# teensy3_5dds.net
KiCad netlist of a schematic drawn in EAGLE
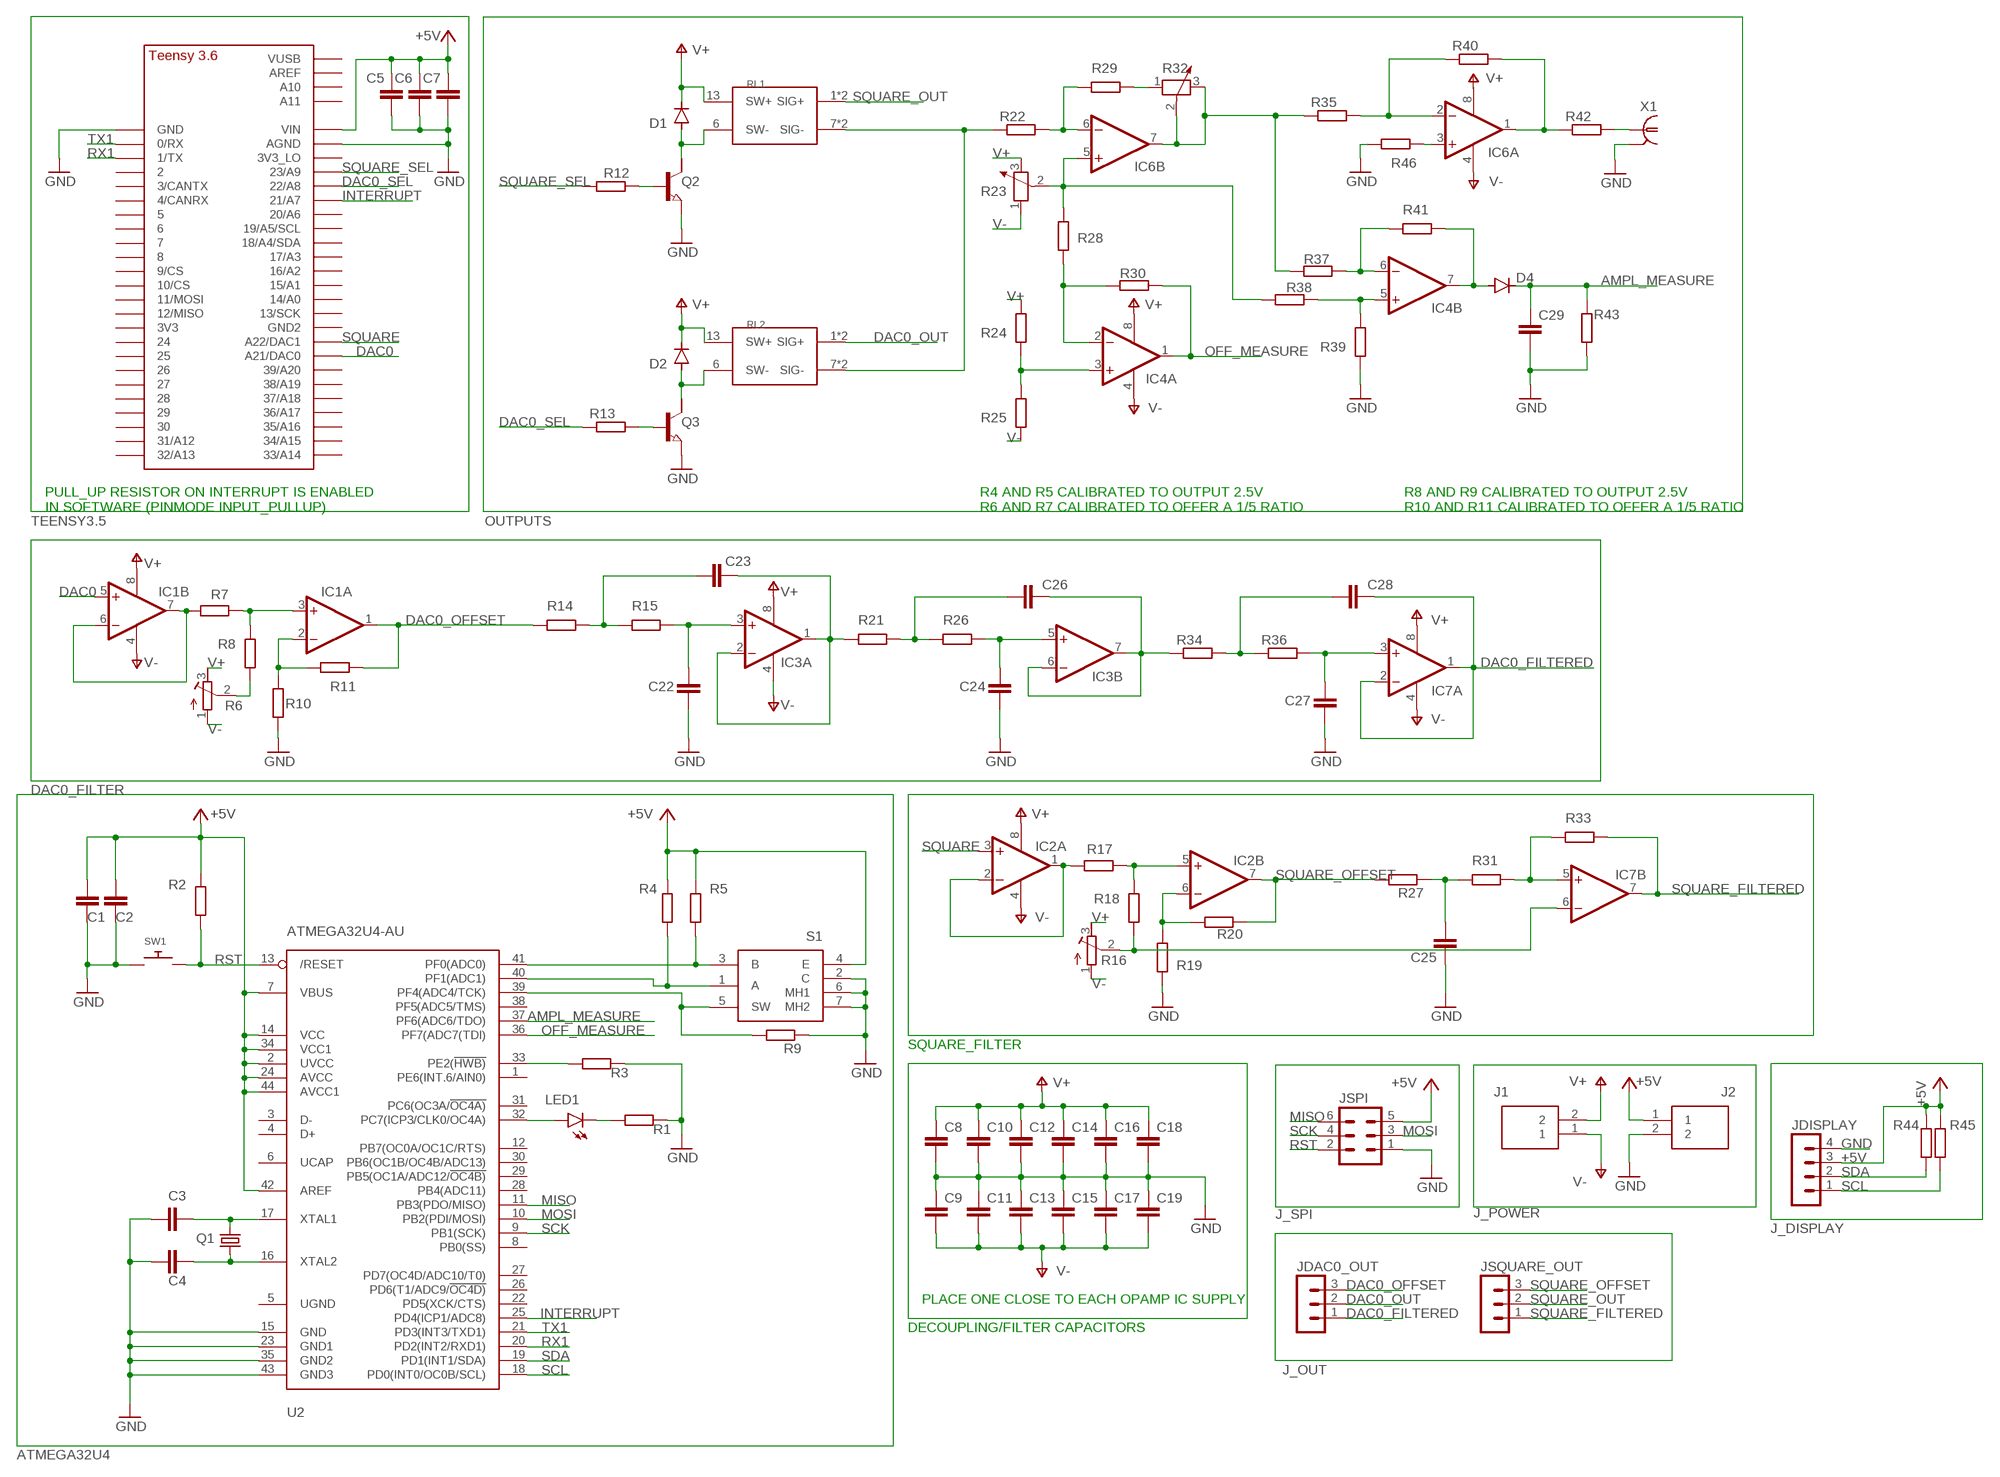
[diagram p0: schematic, sheet 1]

(export (version "E")
  (design (tool "Eeschema 10.0.6"))
  (components
    (comp (ref "C1")
      (value "100u")
      (footprint "eagle-import:C1206")
      (libsource (lib "eagle-import") (part "C-EUC1206"))
    )
    (comp (ref "C2")
      (value "100n")
      (footprint "eagle-import:C0805")
      (libsource (lib "eagle-import") (part "C-EUC0805"))
    )
    (comp (ref "C3")
      (value "22p")
      (footprint "eagle-import:C0805")
      (libsource (lib "eagle-import") (part "C-EUC0805"))
    )
    (comp (ref "C4")
      (value "22p")
      (footprint "eagle-import:C0805")
      (libsource (lib "eagle-import") (part "C-EUC0805"))
    )
    (comp (ref "C5")
      (value "100u")
      (footprint "eagle-import:C1206")
      (libsource (lib "eagle-import") (part "C-EUC1206"))
    )
    (comp (ref "C6")
      (value "100n")
      (footprint "eagle-import:C0805")
      (libsource (lib "eagle-import") (part "C-EUC0805"))
    )
    (comp (ref "C7")
      (value "100n")
      (footprint "eagle-import:C0805")
      (libsource (lib "eagle-import") (part "C-EUC0805"))
    )
    (comp (ref "C8")
      (value "100n")
      (footprint "eagle-import:C0805")
      (libsource (lib "eagle-import") (part "C-EUC0805"))
    )
    (comp (ref "C9")
      (value "100n")
      (footprint "eagle-import:C0805")
      (libsource (lib "eagle-import") (part "C-EUC0805"))
    )
    (comp (ref "C10")
      (value "100n")
      (footprint "eagle-import:C0805")
      (libsource (lib "eagle-import") (part "C-EUC0805"))
    )
    (comp (ref "C11")
      (value "100n")
      (footprint "eagle-import:C0805")
      (libsource (lib "eagle-import") (part "C-EUC0805"))
    )
    (comp (ref "C12")
      (value "100n")
      (footprint "eagle-import:C0805")
      (libsource (lib "eagle-import") (part "C-EUC0805"))
    )
    (comp (ref "C13")
      (value "100n")
      (footprint "eagle-import:C0805")
      (libsource (lib "eagle-import") (part "C-EUC0805"))
    )
    (comp (ref "C14")
      (value "100n")
      (footprint "eagle-import:C0805")
      (libsource (lib "eagle-import") (part "C-EUC0805"))
    )
    (comp (ref "C15")
      (value "100n")
      (footprint "eagle-import:C0805")
      (libsource (lib "eagle-import") (part "C-EUC0805"))
    )
    (comp (ref "C16")
      (value "100n")
      (footprint "eagle-import:C0805")
      (libsource (lib "eagle-import") (part "C-EUC0805"))
    )
    (comp (ref "C17")
      (value "100n")
      (footprint "eagle-import:C0805")
      (libsource (lib "eagle-import") (part "C-EUC0805"))
    )
    (comp (ref "C18")
      (value "100n")
      (footprint "eagle-import:C0805")
      (libsource (lib "eagle-import") (part "C-EUC0805"))
    )
    (comp (ref "C19")
      (value "100n")
      (footprint "eagle-import:C0805")
      (libsource (lib "eagle-import") (part "C-EUC0805"))
    )
    (comp (ref "C22")
      (value "10p")
      (footprint "eagle-import:C0805")
      (libsource (lib "eagle-import") (part "C-EUC0805"))
    )
    (comp (ref "C23")
      (value "150p")
      (footprint "eagle-import:C0805")
      (libsource (lib "eagle-import") (part "C-EUC0805"))
    )
    (comp (ref "C24")
      (value "10p")
      (footprint "eagle-import:C0805")
      (libsource (lib "eagle-import") (part "C-EUC0805"))
    )
    (comp (ref "C25")
      (value "1p")
      (footprint "eagle-import:C0805")
      (libsource (lib "eagle-import") (part "C-EUC0805"))
    )
    (comp (ref "C26")
      (value "100p")
      (footprint "eagle-import:C0805")
      (libsource (lib "eagle-import") (part "C-EUC0805"))
    )
    (comp (ref "C27")
      (value "10p")
      (footprint "eagle-import:C0805")
      (libsource (lib "eagle-import") (part "C-EUC0805"))
    )
    (comp (ref "C28")
      (value "100p")
      (footprint "eagle-import:C0805")
      (libsource (lib "eagle-import") (part "C-EUC0805"))
    )
    (comp (ref "C29")
      (value "C-EUC0805")
      (footprint "eagle-import:C0805")
      (libsource (lib "eagle-import") (part "C-EUC0805"))
    )
    (comp (ref "D1")
      (value "DIODE-SOD323-W")
      (footprint "eagle-import:SOD323-W")
      (libsource (lib "eagle-import") (part "DIODE-SOD323-W"))
    )
    (comp (ref "D2")
      (value "DIODE-SOD323-W")
      (footprint "eagle-import:SOD323-W")
      (libsource (lib "eagle-import") (part "DIODE-SOD323-W"))
    )
    (comp (ref "D4")
      (value "DIODE-SOD123")
      (footprint "eagle-import:SOD123")
      (libsource (lib "eagle-import") (part "DIODE-SOD123"))
    )
    (comp (ref "IC1")
      (value "AD8034")
      (footprint "eagle-import:SO08")
      (libsource (lib "eagle-import") (part "TL082D"))
    )
    (comp (ref "IC2")
      (value "AD8034")
      (footprint "eagle-import:SO08")
      (libsource (lib "eagle-import") (part "TL082D"))
    )
    (comp (ref "IC3")
      (value "AD8034")
      (footprint "eagle-import:SO08")
      (libsource (lib "eagle-import") (part "TL082D"))
    )
    (comp (ref "IC4")
      (value "AD8034")
      (footprint "eagle-import:SO08")
      (libsource (lib "eagle-import") (part "TL082D"))
    )
    (comp (ref "IC6")
      (value "AD8034")
      (footprint "eagle-import:SO08")
      (libsource (lib "eagle-import") (part "TL082D"))
    )
    (comp (ref "IC7")
      (value "AD8034")
      (footprint "eagle-import:SO08")
      (libsource (lib "eagle-import") (part "TL082D"))
    )
    (comp (ref "J1")
      (value "1776275-2")
      (footprint "eagle-import:17762752")
      (libsource (lib "eagle-import") (part "1776275-2"))
    )
    (comp (ref "J2")
      (value "1776275-2")
      (footprint "eagle-import:17762752")
      (libsource (lib "eagle-import") (part "1776275-2"))
    )
    (comp (ref "JDAC0_OUT")
      (value "MA03-1")
      (footprint "eagle-import:MA03-1")
      (libsource (lib "eagle-import") (part "MA03-1"))
    )
    (comp (ref "JDISPLAY")
      (value "MA04-1")
      (footprint "eagle-import:MA04-1")
      (libsource (lib "eagle-import") (part "MA04-1"))
    )
    (comp (ref "JSPI")
      (value "MA03-2")
      (footprint "eagle-import:MA03-2")
      (libsource (lib "eagle-import") (part "MA03-2"))
    )
    (comp (ref "JSQUARE_OUT")
      (value "MA03-1")
      (footprint "eagle-import:MA03-1")
      (libsource (lib "eagle-import") (part "MA03-1"))
    )
    (comp (ref "LED1")
      (value "LEDCHIPLED_1206")
      (footprint "eagle-import:CHIPLED_1206")
      (libsource (lib "eagle-import") (part "LEDCHIPLED_1206"))
    )
    (comp (ref "Q1")
      (value "16MHz")
      (footprint "eagle-import:CSM-7X-DU")
      (libsource (lib "eagle-import") (part "CSM-7X-DU"))
    )
    (comp (ref "Q2")
      (value "NPN-TRANSISTIOR-2COLSOT89")
      (footprint "eagle-import:SOT89")
      (libsource (lib "eagle-import") (part "NPN-TRANSISTIOR-2COLSOT89"))
    )
    (comp (ref "Q3")
      (value "NPN-TRANSISTIOR-2COLSOT89")
      (footprint "eagle-import:SOT89")
      (libsource (lib "eagle-import") (part "NPN-TRANSISTIOR-2COLSOT89"))
    )
    (comp (ref "R1")
      (value "220")
      (footprint "eagle-import:R0805")
      (libsource (lib "eagle-import") (part "R-EU_R0805"))
    )
    (comp (ref "R2")
      (value "10k")
      (footprint "eagle-import:R0805")
      (libsource (lib "eagle-import") (part "R-EU_R0805"))
    )
    (comp (ref "R3")
      (value "10k")
      (footprint "eagle-import:M0805")
      (libsource (lib "eagle-import") (part "R-EU_M0805"))
    )
    (comp (ref "R4")
      (value "10k")
      (footprint "eagle-import:R0805")
      (libsource (lib "eagle-import") (part "R-EU_R0805"))
    )
    (comp (ref "R5")
      (value "10k")
      (footprint "eagle-import:R0805")
      (libsource (lib "eagle-import") (part "R-EU_R0805"))
    )
    (comp (ref "R6")
      (value "100k")
      (footprint "eagle-import:RTRIM3296W")
      (libsource (lib "eagle-import") (part "R-TRIMM3296W"))
    )
    (comp (ref "R7")
      (value "1k")
      (footprint "eagle-import:R0805")
      (libsource (lib "eagle-import") (part "R-EU_R0805"))
    )
    (comp (ref "R8")
      (value "1k")
      (footprint "eagle-import:R0805")
      (libsource (lib "eagle-import") (part "R-EU_R0805"))
    )
    (comp (ref "R9")
      (value "10k")
      (footprint "eagle-import:R0805")
      (libsource (lib "eagle-import") (part "R-EU_R0805"))
    )
    (comp (ref "R10")
      (value "1k")
      (footprint "eagle-import:R0805")
      (libsource (lib "eagle-import") (part "R-EU_R0805"))
    )
    (comp (ref "R11")
      (value "1k")
      (footprint "eagle-import:R0805")
      (libsource (lib "eagle-import") (part "R-EU_R0805"))
    )
    (comp (ref "R12")
      (value "500")
      (footprint "eagle-import:R0805")
      (libsource (lib "eagle-import") (part "R-EU_R0805"))
    )
    (comp (ref "R13")
      (value "500")
      (footprint "eagle-import:R0805")
      (libsource (lib "eagle-import") (part "R-EU_R0805"))
    )
    (comp (ref "R14")
      (value "2.74k")
      (footprint "eagle-import:R0805")
      (libsource (lib "eagle-import") (part "R-EU_R0805"))
    )
    (comp (ref "R15")
      (value "2.74k")
      (footprint "eagle-import:R0805")
      (libsource (lib "eagle-import") (part "R-EU_R0805"))
    )
    (comp (ref "R16")
      (value "100k")
      (footprint "eagle-import:RTRIM3296W")
      (libsource (lib "eagle-import") (part "R-TRIMM3296W"))
    )
    (comp (ref "R17")
      (value "1k")
      (footprint "eagle-import:R0805")
      (libsource (lib "eagle-import") (part "R-EU_R0805"))
    )
    (comp (ref "R18")
      (value "1k")
      (footprint "eagle-import:R0805")
      (libsource (lib "eagle-import") (part "R-EU_R0805"))
    )
    (comp (ref "R19")
      (value "1k")
      (footprint "eagle-import:R0805")
      (libsource (lib "eagle-import") (part "R-EU_R0805"))
    )
    (comp (ref "R20")
      (value "1k")
      (footprint "eagle-import:R0805")
      (libsource (lib "eagle-import") (part "R-EU_R0805"))
    )
    (comp (ref "R21")
      (value "787")
      (footprint "eagle-import:R0805")
      (libsource (lib "eagle-import") (part "R-EU_R0805"))
    )
    (comp (ref "R22")
      (value "1k")
      (footprint "eagle-import:R0805")
      (libsource (lib "eagle-import") (part "R-EU_R0805"))
    )
    (comp (ref "R23")
      (value "10k")
      (footprint "eagle-import:MA03-1")
      (libsource (lib "eagle-import") (part "POTENTIOMETER_VERTICAL"))
    )
    (comp (ref "R24")
      (value "1k")
      (footprint "eagle-import:R0805")
      (libsource (lib "eagle-import") (part "R-EU_R0805"))
    )
    (comp (ref "R25")
      (value "1.5k")
      (footprint "eagle-import:R0805")
      (libsource (lib "eagle-import") (part "R-EU_R0805"))
    )
    (comp (ref "R26")
      (value "14.3k")
      (footprint "eagle-import:R0805")
      (libsource (lib "eagle-import") (part "R-EU_R0805"))
    )
    (comp (ref "R27")
      (value "50")
      (footprint "eagle-import:R0805")
      (libsource (lib "eagle-import") (part "R-EU_R0805"))
    )
    (comp (ref "R28")
      (value "5k")
      (footprint "eagle-import:R0805")
      (libsource (lib "eagle-import") (part "R-EU_R0805"))
    )
    (comp (ref "R29")
      (value "100")
      (footprint "eagle-import:R0805")
      (libsource (lib "eagle-import") (part "R-EU_R0805"))
    )
    (comp (ref "R30")
      (value "1k")
      (footprint "eagle-import:R0805")
      (libsource (lib "eagle-import") (part "R-EU_R0805"))
    )
    (comp (ref "R31")
      (value "2k")
      (footprint "eagle-import:R0805")
      (libsource (lib "eagle-import") (part "R-EU_R0805"))
    )
    (comp (ref "R32")
      (value "10k")
      (footprint "eagle-import:MA03-1")
      (libsource (lib "eagle-import") (part "POTENTIOMETER_VERTICAL"))
    )
    (comp (ref "R33")
      (value "10k")
      (footprint "eagle-import:R0805")
      (libsource (lib "eagle-import") (part "R-EU_R0805"))
    )
    (comp (ref "R34")
      (value "562")
      (footprint "eagle-import:R0805")
      (libsource (lib "eagle-import") (part "R-EU_R0805"))
    )
    (comp (ref "R35")
      (value "R-EU_R0805")
      (footprint "eagle-import:R0805")
      (libsource (lib "eagle-import") (part "R-EU_R0805"))
    )
    (comp (ref "R36")
      (value "20k")
      (footprint "eagle-import:R0805")
      (libsource (lib "eagle-import") (part "R-EU_R0805"))
    )
    (comp (ref "R37")
      (value "5k")
      (footprint "eagle-import:R0805")
      (libsource (lib "eagle-import") (part "R-EU_R0805"))
    )
    (comp (ref "R38")
      (value "10k")
      (footprint "eagle-import:R0805")
      (libsource (lib "eagle-import") (part "R-EU_R0805"))
    )
    (comp (ref "R39")
      (value "14.3k")
      (footprint "eagle-import:R0805")
      (libsource (lib "eagle-import") (part "R-EU_R0805"))
    )
    (comp (ref "R40")
      (value "R-EU_R0805")
      (footprint "eagle-import:R0805")
      (libsource (lib "eagle-import") (part "R-EU_R0805"))
    )
    (comp (ref "R41")
      (value "1k")
      (footprint "eagle-import:R0805")
      (libsource (lib "eagle-import") (part "R-EU_R0805"))
    )
    (comp (ref "R42")
      (value "50")
      (footprint "eagle-import:R0805")
      (libsource (lib "eagle-import") (part "R-EU_R0805"))
    )
    (comp (ref "R43")
      (value "R-EU_R0805")
      (footprint "eagle-import:R0805")
      (libsource (lib "eagle-import") (part "R-EU_R0805"))
    )
    (comp (ref "R44")
      (value "R-EU_R0805")
      (footprint "eagle-import:R0805")
      (libsource (lib "eagle-import") (part "R-EU_R0805"))
    )
    (comp (ref "R45")
      (value "R-EU_R0805")
      (footprint "eagle-import:R0805")
      (libsource (lib "eagle-import") (part "R-EU_R0805"))
    )
    (comp (ref "R46")
      (value "R-EU_R0805")
      (footprint "eagle-import:R0805")
      (libsource (lib "eagle-import") (part "R-EU_R0805"))
    )
    (comp (ref "RL1")
      (value "PRME_15005NOSOCKET")
      (footprint "eagle-import:DIL14")
      (libsource (lib "eagle-import") (part "PRME_15005NOSOCKET"))
    )
    (comp (ref "RL2")
      (value "PRME_15005NOSOCKET")
      (footprint "eagle-import:DIL14")
      (libsource (lib "eagle-import") (part "PRME_15005NOSOCKET"))
    )
    (comp (ref "S1")
      (value "EC11B15242AE")
      (footprint "eagle-import:EC11B15242AE")
      (fields (field (name "MOUSER_PART_NUMBER") "688-EC11B15242AE"))
      (libsource (lib "eagle-import") (part "EC11B15242AE"))
    )
    (comp (ref "SW1")
      (value "SWITCH_PUSHBUTTONC&K_KSS")
      (footprint "eagle-import:BTN_CK_KSS")
      (libsource (lib "eagle-import") (part "SWITCH_PUSHBUTTONC&K_KSS"))
    )
    (comp (ref "U1")
      (value "TEENSY_3.5/3.6_BASIC")
      (footprint "eagle-import:TEENSY_3.5_3.6_BASIC")
      (libsource (lib "eagle-import") (part "TEENSY_3.5/3.6_BASIC"))
    )
    (comp (ref "U2")
      (value "ATMEGA32U4-AU")
      (footprint "eagle-import:TQFP44")
      (libsource (lib "eagle-import") (part "ATMEGA32U4-AU"))
    )
    (comp (ref "X1")
      (value "1-227161-0")
      (footprint "eagle-import:AMP_227161")
      (fields (field (name "MF") "TYCO ELECTRONICS") (field (name "MPN") "1-227161"))
      (libsource (lib "eagle-import") (part "?2271611--0"))
    )
  )
  (nets
    (net (code "1") (name "+5V") (class "Default")
      (node (ref "C1") (pin "1") (pinfunction "1_1") (pintype "passive"))
      (node (ref "C2") (pin "1") (pinfunction "1_1") (pintype "passive"))
      (node (ref "C5") (pin "1") (pinfunction "1_1") (pintype "passive"))
      (node (ref "C6") (pin "1") (pinfunction "1_1") (pintype "passive"))
      (node (ref "C7") (pin "1") (pinfunction "1_1") (pintype "passive"))
      (node (ref "J2") (pin "1") (pinfunction "1_1") (pintype "bidirectional"))
      (node (ref "JDISPLAY") (pin "3") (pinfunction "3_3") (pintype "passive"))
      (node (ref "JSPI") (pin "5") (pinfunction "5_5") (pintype "passive"))
      (node (ref "R2") (pin "2") (pinfunction "2_2") (pintype "passive"))
      (node (ref "R4") (pin "1") (pinfunction "1_1") (pintype "passive"))
      (node (ref "R44") (pin "2") (pinfunction "2_2") (pintype "passive"))
      (node (ref "R45") (pin "1") (pinfunction "1_1") (pintype "passive"))
      (node (ref "R5") (pin "1") (pinfunction "1_1") (pintype "passive"))
      (node (ref "S1") (pin "4") (pinfunction "E_4") (pintype "bidirectional"))
      (node (ref "U1") (pin "VIN") (pinfunction "VIN_VIN") (pintype "bidirectional"))
      (node (ref "U2") (pin "14") (pinfunction "VCC_14") (pintype "bidirectional"))
      (node (ref "U2") (pin "2") (pinfunction "UVCC_2") (pintype "bidirectional"))
      (node (ref "U2") (pin "24") (pinfunction "AVCC_24") (pintype "bidirectional"))
      (node (ref "U2") (pin "34") (pinfunction "VCC1_34") (pintype "bidirectional"))
      (node (ref "U2") (pin "42") (pinfunction "AREF_42") (pintype "bidirectional"))
      (node (ref "U2") (pin "44") (pinfunction "AVCC1_44") (pintype "bidirectional"))
      (node (ref "U2") (pin "7") (pinfunction "VBUS_7") (pintype "bidirectional"))
    )
    (net (code "2") (name "/AMPL_MEASURE") (class "Default")
      (node (ref "C29") (pin "1") (pinfunction "1_1") (pintype "passive"))
      (node (ref "D4") (pin "C") (pinfunction "C_C") (pintype "passive"))
      (node (ref "R43") (pin "2") (pinfunction "2_2") (pintype "passive"))
      (node (ref "U2") (pin "37") (pinfunction "PF6(ADC6/TDO)_37") (pintype "bidirectional"))
    )
    (net (code "4") (name "/DAC0") (class "Default")
      (node (ref "IC1") (pin "5") (pinfunction "+IN_5") (pintype "input"))
      (node (ref "U1") (pin "21/DAC0") (pinfunction "A21/DAC0_21/DAC0") (pintype "bidirectional"))
    )
    (net (code "6") (name "/DAC0_FILTERED") (class "Default")
      (node (ref "C28") (pin "1") (pinfunction "1_1") (pintype "passive"))
      (node (ref "IC7") (pin "1") (pinfunction "OUT_1") (pintype "output"))
      (node (ref "IC7") (pin "2") (pinfunction "-IN_2") (pintype "input"))
      (node (ref "JDAC0_OUT") (pin "1") (pinfunction "1_1") (pintype "passive"))
    )
    (net (code "7") (name "/DAC0_OFFSET") (class "Default")
      (node (ref "IC1") (pin "1") (pinfunction "OUT_1") (pintype "output"))
      (node (ref "JDAC0_OUT") (pin "3") (pinfunction "3_3") (pintype "passive"))
      (node (ref "R11") (pin "1") (pinfunction "1_1") (pintype "passive"))
      (node (ref "R14") (pin "1") (pinfunction "1_1") (pintype "passive"))
    )
    (net (code "8") (name "/DAC0_OUT") (class "Default")
      (node (ref "JDAC0_OUT") (pin "2") (pinfunction "2_2") (pintype "passive"))
      (node (ref "RL2") (pin "1") (pinfunction "SIG+_1") (pintype "bidirectional"))
      (node (ref "RL2") (pin "14") (pinfunction "SIG+_14") (pintype "bidirectional"))
    )
    (net (code "9") (name "/DAC0_SEL") (class "Default")
      (node (ref "R13") (pin "1") (pinfunction "1_1") (pintype "passive"))
      (node (ref "U1") (pin "22/A8") (pinfunction "22/A8_22/A8") (pintype "bidirectional"))
    )
    (net (code "10") (name "/INTERRUPT") (class "Default")
      (node (ref "U1") (pin "21/A7") (pinfunction "21/A7_21/A7") (pintype "bidirectional"))
      (node (ref "U2") (pin "25") (pinfunction "PD4(ICP1/ADC8)_25") (pintype "bidirectional"))
    )
    (net (code "15") (name "/MISO") (class "Default")
      (node (ref "JSPI") (pin "6") (pinfunction "6_6") (pintype "passive"))
      (node (ref "U2") (pin "11") (pinfunction "PB3(PDO/MISO)_11") (pintype "bidirectional"))
    )
    (net (code "16") (name "/MOSI") (class "Default")
      (node (ref "JSPI") (pin "3") (pinfunction "3_3") (pintype "passive"))
      (node (ref "U2") (pin "10") (pinfunction "PB2(PDI/MOSI)_10") (pintype "bidirectional"))
    )
    (net (code "17") (name "/OFF_MEASURE") (class "Default")
      (node (ref "IC4") (pin "1") (pinfunction "OUT_1") (pintype "output"))
      (node (ref "R30") (pin "1") (pinfunction "1_1") (pintype "passive"))
      (node (ref "U2") (pin "36") (pinfunction "PF7(ADC7(TDI)_36") (pintype "bidirectional"))
    )
    (net (code "19") (name "/RST") (class "Default")
      (node (ref "JSPI") (pin "2") (pinfunction "2_2") (pintype "passive"))
      (node (ref "R2") (pin "1") (pinfunction "1_1") (pintype "passive"))
      (node (ref "SW1") (pin "P$2") (pinfunction "P$2_P$2") (pintype "passive"))
      (node (ref "U2") (pin "13") (pinfunction "/RESET_13") (pintype "bidirectional"))
    )
    (net (code "20") (name "/RX1") (class "Default")
      (node (ref "U1") (pin "1/TX") (pinfunction "1/TX_1/TX") (pintype "bidirectional"))
      (node (ref "U2") (pin "20") (pinfunction "PD2(INT2/RXD1)_20") (pintype "bidirectional"))
    )
    (net (code "21") (name "/SCK") (class "Default")
      (node (ref "JSPI") (pin "4") (pinfunction "4_4") (pintype "passive"))
      (node (ref "U2") (pin "9") (pinfunction "PB1(SCK)_9") (pintype "bidirectional"))
    )
    (net (code "22") (name "/SCL") (class "Default")
      (node (ref "JDISPLAY") (pin "1") (pinfunction "1_1") (pintype "passive"))
      (node (ref "R45") (pin "2") (pinfunction "2_2") (pintype "passive"))
      (node (ref "U2") (pin "18") (pinfunction "PD0(INT0/OC0B/SCL)_18") (pintype "bidirectional"))
    )
    (net (code "23") (name "/SDA") (class "Default")
      (node (ref "JDISPLAY") (pin "2") (pinfunction "2_2") (pintype "passive"))
      (node (ref "R44") (pin "1") (pinfunction "1_1") (pintype "passive"))
      (node (ref "U2") (pin "19") (pinfunction "PD1(INT1/SDA)_19") (pintype "bidirectional"))
    )
    (net (code "24") (name "/SQUARE") (class "Default")
      (node (ref "IC2") (pin "3") (pinfunction "+IN_3") (pintype "input"))
      (node (ref "U1") (pin "A22/DAC1") (pinfunction "A22/DAC1_A22/DAC1") (pintype "bidirectional"))
    )
    (net (code "25") (name "/SQUARE_FILTERED") (class "Default")
      (node (ref "IC7") (pin "7") (pinfunction "OUT_7") (pintype "output"))
      (node (ref "JSQUARE_OUT") (pin "1") (pinfunction "1_1") (pintype "passive"))
      (node (ref "R33") (pin "2") (pinfunction "2_2") (pintype "passive"))
    )
    (net (code "26") (name "/SQUARE_OFFSET") (class "Default")
      (node (ref "IC2") (pin "7") (pinfunction "OUT_7") (pintype "output"))
      (node (ref "JSQUARE_OUT") (pin "3") (pinfunction "3_3") (pintype "passive"))
      (node (ref "R20") (pin "1") (pinfunction "1_1") (pintype "passive"))
      (node (ref "R27") (pin "2") (pinfunction "2_2") (pintype "passive"))
    )
    (net (code "27") (name "/SQUARE_OUT") (class "Default")
      (node (ref "JSQUARE_OUT") (pin "2") (pinfunction "2_2") (pintype "passive"))
      (node (ref "RL1") (pin "1") (pinfunction "SIG+_1") (pintype "bidirectional"))
      (node (ref "RL1") (pin "14") (pinfunction "SIG+_14") (pintype "bidirectional"))
    )
    (net (code "28") (name "/SQUARE_SEL") (class "Default")
      (node (ref "R12") (pin "1") (pinfunction "1_1") (pintype "passive"))
      (node (ref "U1") (pin "23/A9") (pinfunction "23/A9_23/A9") (pintype "bidirectional"))
    )
    (net (code "30") (name "/TX1") (class "Default")
      (node (ref "U1") (pin "0/RX") (pinfunction "0/RX_0/RX") (pintype "bidirectional"))
      (node (ref "U2") (pin "21") (pinfunction "PD3(INT3/TXD1)_21") (pintype "bidirectional"))
    )
    (net (code "31") (name "GND") (class "Default")
      (node (ref "C1") (pin "2") (pinfunction "2_2") (pintype "passive"))
      (node (ref "C10") (pin "2") (pinfunction "2_2") (pintype "passive"))
      (node (ref "C11") (pin "1") (pinfunction "1_1") (pintype "passive"))
      (node (ref "C12") (pin "2") (pinfunction "2_2") (pintype "passive"))
      (node (ref "C13") (pin "1") (pinfunction "1_1") (pintype "passive"))
      (node (ref "C14") (pin "2") (pinfunction "2_2") (pintype "passive"))
      (node (ref "C15") (pin "1") (pinfunction "1_1") (pintype "passive"))
      (node (ref "C16") (pin "2") (pinfunction "2_2") (pintype "passive"))
      (node (ref "C17") (pin "1") (pinfunction "1_1") (pintype "passive"))
      (node (ref "C18") (pin "2") (pinfunction "2_2") (pintype "passive"))
      (node (ref "C19") (pin "1") (pinfunction "1_1") (pintype "passive"))
      (node (ref "C2") (pin "2") (pinfunction "2_2") (pintype "passive"))
      (node (ref "C22") (pin "1") (pinfunction "1_1") (pintype "passive"))
      (node (ref "C24") (pin "1") (pinfunction "1_1") (pintype "passive"))
      (node (ref "C25") (pin "1") (pinfunction "1_1") (pintype "passive"))
      (node (ref "C27") (pin "1") (pinfunction "1_1") (pintype "passive"))
      (node (ref "C29") (pin "2") (pinfunction "2_2") (pintype "passive"))
      (node (ref "C3") (pin "1") (pinfunction "1_1") (pintype "passive"))
      (node (ref "C4") (pin "1") (pinfunction "1_1") (pintype "passive"))
      (node (ref "C5") (pin "2") (pinfunction "2_2") (pintype "passive"))
      (node (ref "C6") (pin "2") (pinfunction "2_2") (pintype "passive"))
      (node (ref "C7") (pin "2") (pinfunction "2_2") (pintype "passive"))
      (node (ref "C8") (pin "2") (pinfunction "2_2") (pintype "passive"))
      (node (ref "C9") (pin "1") (pinfunction "1_1") (pintype "passive"))
      (node (ref "J2") (pin "2") (pinfunction "2_2") (pintype "bidirectional"))
      (node (ref "JDISPLAY") (pin "4") (pinfunction "4_4") (pintype "passive"))
      (node (ref "JSPI") (pin "1") (pinfunction "1_1") (pintype "passive"))
      (node (ref "Q2") (pin "3") (pinfunction "E_3") (pintype "passive"))
      (node (ref "Q3") (pin "3") (pinfunction "E_3") (pintype "passive"))
      (node (ref "R1") (pin "1") (pinfunction "1_1") (pintype "passive"))
      (node (ref "R10") (pin "2") (pinfunction "2_2") (pintype "passive"))
      (node (ref "R19") (pin "2") (pinfunction "2_2") (pintype "passive"))
      (node (ref "R3") (pin "2") (pinfunction "2_2") (pintype "passive"))
      (node (ref "R39") (pin "2") (pinfunction "2_2") (pintype "passive"))
      (node (ref "R43") (pin "1") (pinfunction "1_1") (pintype "passive"))
      (node (ref "R46") (pin "1") (pinfunction "1_1") (pintype "passive"))
      (node (ref "R9") (pin "1") (pinfunction "1_1") (pintype "passive"))
      (node (ref "S1") (pin "2") (pinfunction "C_2") (pintype "bidirectional"))
      (node (ref "S1") (pin "6") (pinfunction "MH1_6") (pintype "bidirectional"))
      (node (ref "S1") (pin "7") (pinfunction "MH2_7") (pintype "bidirectional"))
      (node (ref "SW1") (pin "P$1") (pinfunction "P$1_P$1") (pintype "passive"))
      (node (ref "U1") (pin "AGND") (pinfunction "AGND_AGND") (pintype "bidirectional"))
      (node (ref "U1") (pin "GND") (pinfunction "GND_GND") (pintype "bidirectional"))
      (node (ref "U2") (pin "15") (pinfunction "GND_15") (pintype "bidirectional"))
      (node (ref "U2") (pin "23") (pinfunction "GND1_23") (pintype "bidirectional"))
      (node (ref "U2") (pin "35") (pinfunction "GND2_35") (pintype "bidirectional"))
      (node (ref "U2") (pin "43") (pinfunction "GND3_43") (pintype "bidirectional"))
      (node (ref "X1") (pin "2") (pinfunction "2_2") (pintype "passive"))
    )
    (net (code "32") (name "Net-(C23-Pad2)") (class "Default")
      (node (ref "C23") (pin "2") (pinfunction "2_2") (pintype "passive"))
      (node (ref "R14") (pin "2") (pinfunction "2_2") (pintype "passive"))
      (node (ref "R15") (pin "1") (pinfunction "1_1") (pintype "passive"))
    )
    (net (code "33") (name "Net-(C25-Pad2)") (class "Default")
      (node (ref "C25") (pin "2") (pinfunction "2_2") (pintype "passive"))
      (node (ref "R27") (pin "1") (pinfunction "1_1") (pintype "passive"))
      (node (ref "R31") (pin "1") (pinfunction "1_1") (pintype "passive"))
    )
    (net (code "34") (name "Net-(C26-Pad1)") (class "Default")
      (node (ref "C26") (pin "1") (pinfunction "1_1") (pintype "passive"))
      (node (ref "R21") (pin "2") (pinfunction "2_2") (pintype "passive"))
      (node (ref "R26") (pin "1") (pinfunction "1_1") (pintype "passive"))
    )
    (net (code "35") (name "Net-(C28-Pad2)") (class "Default")
      (node (ref "C28") (pin "2") (pinfunction "2_2") (pintype "passive"))
      (node (ref "R34") (pin "2") (pinfunction "2_2") (pintype "passive"))
      (node (ref "R36") (pin "1") (pinfunction "1_1") (pintype "passive"))
    )
    (net (code "36") (name "Net-(IC1A-+IN)") (class "Default")
      (node (ref "IC1") (pin "3") (pinfunction "+IN_3") (pintype "input"))
      (node (ref "R7") (pin "2") (pinfunction "2_2") (pintype "passive"))
      (node (ref "R8") (pin "2") (pinfunction "2_2") (pintype "passive"))
    )
    (net (code "37") (name "Net-(IC1A--IN)") (class "Default")
      (node (ref "IC1") (pin "2") (pinfunction "-IN_2") (pintype "input"))
      (node (ref "R10") (pin "1") (pinfunction "1_1") (pintype "passive"))
      (node (ref "R11") (pin "2") (pinfunction "2_2") (pintype "passive"))
    )
    (net (code "38") (name "Net-(IC1B--IN)") (class "Default")
      (node (ref "IC1") (pin "6") (pinfunction "-IN_6") (pintype "input"))
      (node (ref "IC1") (pin "7") (pinfunction "OUT_7") (pintype "output"))
      (node (ref "R7") (pin "1") (pinfunction "1_1") (pintype "passive"))
    )
    (net (code "39") (name "Net-(IC2A--IN)") (class "Default")
      (node (ref "IC2") (pin "1") (pinfunction "OUT_1") (pintype "output"))
      (node (ref "IC2") (pin "2") (pinfunction "-IN_2") (pintype "input"))
      (node (ref "R17") (pin "1") (pinfunction "1_1") (pintype "passive"))
    )
    (net (code "40") (name "Net-(IC2B-+IN)") (class "Default")
      (node (ref "IC2") (pin "5") (pinfunction "+IN_5") (pintype "input"))
      (node (ref "R17") (pin "2") (pinfunction "2_2") (pintype "passive"))
      (node (ref "R18") (pin "2") (pinfunction "2_2") (pintype "passive"))
    )
    (net (code "41") (name "Net-(IC2B--IN)") (class "Default")
      (node (ref "IC2") (pin "6") (pinfunction "-IN_6") (pintype "input"))
      (node (ref "R19") (pin "1") (pinfunction "1_1") (pintype "passive"))
      (node (ref "R20") (pin "2") (pinfunction "2_2") (pintype "passive"))
    )
    (net (code "42") (name "Net-(IC3A-+IN)") (class "Default")
      (node (ref "C22") (pin "2") (pinfunction "2_2") (pintype "passive"))
      (node (ref "IC3") (pin "3") (pinfunction "+IN_3") (pintype "input"))
      (node (ref "R15") (pin "2") (pinfunction "2_2") (pintype "passive"))
    )
    (net (code "43") (name "Net-(IC3A--IN)") (class "Default")
      (node (ref "C23") (pin "1") (pinfunction "1_1") (pintype "passive"))
      (node (ref "IC3") (pin "1") (pinfunction "OUT_1") (pintype "output"))
      (node (ref "IC3") (pin "2") (pinfunction "-IN_2") (pintype "input"))
      (node (ref "R21") (pin "1") (pinfunction "1_1") (pintype "passive"))
    )
    (net (code "44") (name "Net-(IC3B-+IN)") (class "Default")
      (node (ref "C24") (pin "2") (pinfunction "2_2") (pintype "passive"))
      (node (ref "IC3") (pin "5") (pinfunction "+IN_5") (pintype "input"))
      (node (ref "R26") (pin "2") (pinfunction "2_2") (pintype "passive"))
    )
    (net (code "45") (name "Net-(IC3B--IN)") (class "Default")
      (node (ref "C26") (pin "2") (pinfunction "2_2") (pintype "passive"))
      (node (ref "IC3") (pin "6") (pinfunction "-IN_6") (pintype "input"))
      (node (ref "IC3") (pin "7") (pinfunction "OUT_7") (pintype "output"))
      (node (ref "R34") (pin "1") (pinfunction "1_1") (pintype "passive"))
    )
    (net (code "46") (name "Net-(IC4A-+IN)") (class "Default")
      (node (ref "IC4") (pin "3") (pinfunction "+IN_3") (pintype "input"))
      (node (ref "R24") (pin "1") (pinfunction "1_1") (pintype "passive"))
      (node (ref "R25") (pin "2") (pinfunction "2_2") (pintype "passive"))
    )
    (net (code "47") (name "Net-(IC4A--IN)") (class "Default")
      (node (ref "IC4") (pin "2") (pinfunction "-IN_2") (pintype "input"))
      (node (ref "R28") (pin "2") (pinfunction "2_2") (pintype "passive"))
      (node (ref "R30") (pin "2") (pinfunction "2_2") (pintype "passive"))
    )
    (net (code "48") (name "Net-(IC4B-+IN)") (class "Default")
      (node (ref "IC4") (pin "5") (pinfunction "+IN_5") (pintype "input"))
      (node (ref "R38") (pin "2") (pinfunction "2_2") (pintype "passive"))
      (node (ref "R39") (pin "1") (pinfunction "1_1") (pintype "passive"))
    )
    (net (code "49") (name "Net-(IC4B--IN)") (class "Default")
      (node (ref "IC4") (pin "6") (pinfunction "-IN_6") (pintype "input"))
      (node (ref "R37") (pin "2") (pinfunction "2_2") (pintype "passive"))
      (node (ref "R41") (pin "1") (pinfunction "1_1") (pintype "passive"))
    )
    (net (code "50") (name "Net-(IC4B-OUT)") (class "Default")
      (node (ref "D4") (pin "A") (pinfunction "A_A") (pintype "passive"))
      (node (ref "IC4") (pin "7") (pinfunction "OUT_7") (pintype "output"))
      (node (ref "R41") (pin "2") (pinfunction "2_2") (pintype "passive"))
    )
    (net (code "51") (name "Net-(IC6A-+IN)") (class "Default")
      (node (ref "IC6") (pin "3") (pinfunction "+IN_3") (pintype "input"))
      (node (ref "R46") (pin "2") (pinfunction "2_2") (pintype "passive"))
    )
    (net (code "52") (name "Net-(IC6A--IN)") (class "Default")
      (node (ref "IC6") (pin "2") (pinfunction "-IN_2") (pintype "input"))
      (node (ref "R35") (pin "2") (pinfunction "2_2") (pintype "passive"))
      (node (ref "R40") (pin "1") (pinfunction "1_1") (pintype "passive"))
    )
    (net (code "53") (name "Net-(IC6A-OUT)") (class "Default")
      (node (ref "IC6") (pin "1") (pinfunction "OUT_1") (pintype "output"))
      (node (ref "R40") (pin "2") (pinfunction "2_2") (pintype "passive"))
      (node (ref "R42") (pin "1") (pinfunction "1_1") (pintype "passive"))
    )
    (net (code "54") (name "Net-(IC6B-+IN)") (class "Default")
      (node (ref "IC6") (pin "5") (pinfunction "+IN_5") (pintype "input"))
      (node (ref "R23") (pin "2") (pinfunction "3_2") (pintype "passive"))
      (node (ref "R28") (pin "1") (pinfunction "1_1") (pintype "passive"))
      (node (ref "R38") (pin "1") (pinfunction "1_1") (pintype "passive"))
    )
    (net (code "55") (name "Net-(IC6B--IN)") (class "Default")
      (node (ref "IC6") (pin "6") (pinfunction "-IN_6") (pintype "input"))
      (node (ref "R22") (pin "2") (pinfunction "2_2") (pintype "passive"))
      (node (ref "R29") (pin "1") (pinfunction "1_1") (pintype "passive"))
    )
    (net (code "56") (name "Net-(IC6B-OUT)") (class "Default")
      (node (ref "IC6") (pin "7") (pinfunction "OUT_7") (pintype "output"))
      (node (ref "R32") (pin "2") (pinfunction "3_2") (pintype "passive"))
      (node (ref "R32") (pin "3") (pinfunction "2_3") (pintype "passive"))
      (node (ref "R35") (pin "1") (pinfunction "1_1") (pintype "passive"))
      (node (ref "R37") (pin "1") (pinfunction "1_1") (pintype "passive"))
    )
    (net (code "57") (name "Net-(IC7A-+IN)") (class "Default")
      (node (ref "C27") (pin "2") (pinfunction "2_2") (pintype "passive"))
      (node (ref "IC7") (pin "3") (pinfunction "+IN_3") (pintype "input"))
      (node (ref "R36") (pin "2") (pinfunction "2_2") (pintype "passive"))
    )
    (net (code "58") (name "Net-(IC7B-+IN)") (class "Default")
      (node (ref "IC7") (pin "5") (pinfunction "+IN_5") (pintype "input"))
      (node (ref "R31") (pin "2") (pinfunction "2_2") (pintype "passive"))
      (node (ref "R33") (pin "1") (pinfunction "1_1") (pintype "passive"))
    )
    (net (code "59") (name "Net-(IC7B--IN)") (class "Default")
      (node (ref "IC7") (pin "6") (pinfunction "-IN_6") (pintype "input"))
      (node (ref "R16") (pin "2") (pinfunction "S_2") (pintype "passive"))
      (node (ref "R18") (pin "1") (pinfunction "1_1") (pintype "passive"))
    )
    (net (code "60") (name "Net-(LED1-PadC)") (class "Default")
      (node (ref "LED1") (pin "C") (pinfunction "C_C") (pintype "passive"))
      (node (ref "R1") (pin "2") (pinfunction "2_2") (pintype "passive"))
    )
    (net (code "61") (name "Net-(Q2-B)") (class "Default")
      (node (ref "Q2") (pin "1") (pinfunction "B_1") (pintype "passive"))
      (node (ref "R12") (pin "2") (pinfunction "2_2") (pintype "passive"))
    )
    (net (code "62") (name "Net-(Q2-C)") (class "Default")
      (node (ref "D1") (pin "A") (pinfunction "A_A") (pintype "passive"))
      (node (ref "Q2") (pin "2") (pinfunction "C_2") (pintype "passive"))
      (node (ref "RL1") (pin "6") (pinfunction "SW-_6") (pintype "bidirectional"))
    )
    (net (code "63") (name "Net-(Q3-B)") (class "Default")
      (node (ref "Q3") (pin "1") (pinfunction "B_1") (pintype "passive"))
      (node (ref "R13") (pin "2") (pinfunction "2_2") (pintype "passive"))
    )
    (net (code "64") (name "Net-(Q3-C)") (class "Default")
      (node (ref "D2") (pin "A") (pinfunction "A_A") (pintype "passive"))
      (node (ref "Q3") (pin "2") (pinfunction "C_2") (pintype "passive"))
      (node (ref "RL2") (pin "6") (pinfunction "SW-_6") (pintype "bidirectional"))
    )
    (net (code "65") (name "Net-(R6-S)") (class "Default")
      (node (ref "R6") (pin "2") (pinfunction "S_2") (pintype "passive"))
      (node (ref "R8") (pin "1") (pinfunction "1_1") (pintype "passive"))
    )
    (net (code "66") (name "Net-(R22-Pad1)") (class "Default")
      (node (ref "R22") (pin "1") (pinfunction "1_1") (pintype "passive"))
      (node (ref "RL1") (pin "7") (pinfunction "SIG-_7") (pintype "bidirectional"))
      (node (ref "RL1") (pin "8") (pinfunction "SIG-_8") (pintype "bidirectional"))
      (node (ref "RL2") (pin "7") (pinfunction "SIG-_7") (pintype "bidirectional"))
      (node (ref "RL2") (pin "8") (pinfunction "SIG-_8") (pintype "bidirectional"))
    )
    (net (code "67") (name "Net-(R29-Pad2)") (class "Default")
      (node (ref "R29") (pin "2") (pinfunction "2_2") (pintype "passive"))
      (node (ref "R32") (pin "1") (pinfunction "1_1") (pintype "passive"))
    )
    (net (code "68") (name "Net-(R42-Pad2)") (class "Default")
      (node (ref "R42") (pin "2") (pinfunction "2_2") (pintype "passive"))
      (node (ref "X1") (pin "1") (pinfunction "1_1") (pintype "passive"))
    )
    (net (code "69") (name "Net-(S1-A)") (class "Default")
      (node (ref "R4") (pin "2") (pinfunction "2_2") (pintype "passive"))
      (node (ref "S1") (pin "1") (pinfunction "A_1") (pintype "bidirectional"))
      (node (ref "U2") (pin "40") (pinfunction "PF1(ADC1)_40") (pintype "bidirectional"))
    )
    (net (code "70") (name "Net-(S1-B)") (class "Default")
      (node (ref "R5") (pin "2") (pinfunction "2_2") (pintype "passive"))
      (node (ref "S1") (pin "3") (pinfunction "B_3") (pintype "bidirectional"))
      (node (ref "U2") (pin "41") (pinfunction "PF0(ADC0)_41") (pintype "bidirectional"))
    )
    (net (code "71") (name "Net-(S1-SW)") (class "Default")
      (node (ref "R9") (pin "2") (pinfunction "2_2") (pintype "passive"))
      (node (ref "S1") (pin "5") (pinfunction "SW_5") (pintype "bidirectional"))
      (node (ref "U2") (pin "39") (pinfunction "PF4(ADC4/TCK)_39") (pintype "bidirectional"))
    )
    (net (code "72") (name "Net-(U2-PC7(ICP3{slash}CLK0{slash}OC4A))") (class "Default")
      (node (ref "LED1") (pin "A") (pinfunction "A_A") (pintype "passive"))
      (node (ref "U2") (pin "32") (pinfunction "PC7(ICP3/CLK0/OC4A)_32") (pintype "bidirectional"))
    )
    (net (code "73") (name "Net-(U2-PE2(~{HWB}))") (class "Default")
      (node (ref "R3") (pin "1") (pinfunction "1_1") (pintype "passive"))
      (node (ref "U2") (pin "33") (pinfunction "PE2(~{HWB})_33") (pintype "bidirectional"))
    )
    (net (code "74") (name "Net-(U2-XTAL1)") (class "Default")
      (node (ref "C3") (pin "2") (pinfunction "2_2") (pintype "passive"))
      (node (ref "Q1") (pin "2") (pinfunction "2_2") (pintype "passive"))
      (node (ref "U2") (pin "17") (pinfunction "XTAL1_17") (pintype "bidirectional"))
    )
    (net (code "75") (name "Net-(U2-XTAL2)") (class "Default")
      (node (ref "C4") (pin "2") (pinfunction "2_2") (pintype "passive"))
      (node (ref "Q1") (pin "1") (pinfunction "1_1") (pintype "passive"))
      (node (ref "U2") (pin "16") (pinfunction "XTAL2_16") (pintype "bidirectional"))
    )
    (net (code "76") (name "V+") (class "Default")
      (node (ref "C10") (pin "1") (pinfunction "1_1") (pintype "passive"))
      (node (ref "C12") (pin "1") (pinfunction "1_1") (pintype "passive"))
      (node (ref "C14") (pin "1") (pinfunction "1_1") (pintype "passive"))
      (node (ref "C16") (pin "1") (pinfunction "1_1") (pintype "passive"))
      (node (ref "C18") (pin "1") (pinfunction "1_1") (pintype "passive"))
      (node (ref "C8") (pin "1") (pinfunction "1_1") (pintype "passive"))
      (node (ref "D1") (pin "C") (pinfunction "C_C") (pintype "passive"))
      (node (ref "D2") (pin "C") (pinfunction "C_C") (pintype "passive"))
      (node (ref "IC1") (pin "8") (pinfunction "V+_8") (pintype "power_in"))
      (node (ref "IC2") (pin "8") (pinfunction "V+_8") (pintype "power_in"))
      (node (ref "IC3") (pin "8") (pinfunction "V+_8") (pintype "power_in"))
      (node (ref "IC4") (pin "8") (pinfunction "V+_8") (pintype "power_in"))
      (node (ref "IC6") (pin "8") (pinfunction "V+_8") (pintype "power_in"))
      (node (ref "IC7") (pin "8") (pinfunction "V+_8") (pintype "power_in"))
      (node (ref "J1") (pin "2") (pinfunction "2_2") (pintype "bidirectional"))
      (node (ref "R16") (pin "3") (pinfunction "E_3") (pintype "passive"))
      (node (ref "R23") (pin "3") (pinfunction "2_3") (pintype "passive"))
      (node (ref "R24") (pin "2") (pinfunction "2_2") (pintype "passive"))
      (node (ref "R6") (pin "3") (pinfunction "E_3") (pintype "passive"))
      (node (ref "RL1") (pin "13") (pinfunction "SW+_13") (pintype "bidirectional"))
      (node (ref "RL2") (pin "13") (pinfunction "SW+_13") (pintype "bidirectional"))
    )
    (net (code "77") (name "V-") (class "Default")
      (node (ref "C11") (pin "2") (pinfunction "2_2") (pintype "passive"))
      (node (ref "C13") (pin "2") (pinfunction "2_2") (pintype "passive"))
      (node (ref "C15") (pin "2") (pinfunction "2_2") (pintype "passive"))
      (node (ref "C17") (pin "2") (pinfunction "2_2") (pintype "passive"))
      (node (ref "C19") (pin "2") (pinfunction "2_2") (pintype "passive"))
      (node (ref "C9") (pin "2") (pinfunction "2_2") (pintype "passive"))
      (node (ref "IC1") (pin "4") (pinfunction "V-_4") (pintype "power_in"))
      (node (ref "IC2") (pin "4") (pinfunction "V-_4") (pintype "power_in"))
      (node (ref "IC3") (pin "4") (pinfunction "V-_4") (pintype "power_in"))
      (node (ref "IC4") (pin "4") (pinfunction "V-_4") (pintype "power_in"))
      (node (ref "IC6") (pin "4") (pinfunction "V-_4") (pintype "power_in"))
      (node (ref "IC7") (pin "4") (pinfunction "V-_4") (pintype "power_in"))
      (node (ref "J1") (pin "1") (pinfunction "1_1") (pintype "bidirectional"))
      (node (ref "R16") (pin "1") (pinfunction "A_1") (pintype "passive"))
      (node (ref "R23") (pin "1") (pinfunction "1_1") (pintype "passive"))
      (node (ref "R25") (pin "1") (pinfunction "1_1") (pintype "passive"))
      (node (ref "R6") (pin "1") (pinfunction "A_1") (pintype "passive"))
    )
    (net (code "78") (name "unconnected-(Q2-C{slash}-Pad2@1)") (class "Default")
      (node (ref "Q2") (pin "2@1") (pinfunction "C/_2@1") (pintype "passive"))
    )
    (net (code "79") (name "unconnected-(Q3-C{slash}-Pad2@1)") (class "Default")
      (node (ref "Q3") (pin "2@1") (pinfunction "C/_2@1") (pintype "passive"))
    )
    (net (code "80") (name "unconnected-(U1-Pad2)") (class "Default")
      (node (ref "U1") (pin "2") (pinfunction "2_2") (pintype "bidirectional"))
    )
    (net (code "81") (name "unconnected-(U1-Pad3V3)") (class "Default")
      (node (ref "U1") (pin "3V3") (pinfunction "3V3_3V3") (pintype "bidirectional"))
    )
    (net (code "82") (name "unconnected-(U1-Pad3V3_LO)") (class "Default")
      (node (ref "U1") (pin "3V3_LO") (pinfunction "3V3_LO_3V3_LO") (pintype "bidirectional"))
    )
    (net (code "83") (name "unconnected-(U1-Pad3{slash}CANTX)") (class "Default")
      (node (ref "U1") (pin "3/CANTX") (pinfunction "3/CANTX_3/CANTX") (pintype "bidirectional"))
    )
    (net (code "84") (name "unconnected-(U1-Pad4{slash}CANRX)") (class "Default")
      (node (ref "U1") (pin "4/CANRX") (pinfunction "4/CANRX_4/CANRX") (pintype "bidirectional"))
    )
    (net (code "85") (name "unconnected-(U1-Pad5)") (class "Default")
      (node (ref "U1") (pin "5") (pinfunction "5_5") (pintype "bidirectional"))
    )
    (net (code "86") (name "unconnected-(U1-Pad6)") (class "Default")
      (node (ref "U1") (pin "6") (pinfunction "6_6") (pintype "bidirectional"))
    )
    (net (code "87") (name "unconnected-(U1-Pad7)") (class "Default")
      (node (ref "U1") (pin "7") (pinfunction "7_7") (pintype "bidirectional"))
    )
    (net (code "88") (name "unconnected-(U1-Pad8)") (class "Default")
      (node (ref "U1") (pin "8") (pinfunction "8_8") (pintype "bidirectional"))
    )
    (net (code "89") (name "unconnected-(U1-Pad9{slash}CS)") (class "Default")
      (node (ref "U1") (pin "9/CS") (pinfunction "9/CS_9/CS") (pintype "bidirectional"))
    )
    (net (code "90") (name "unconnected-(U1-Pad10{slash}CS)") (class "Default")
      (node (ref "U1") (pin "10/CS") (pinfunction "10/CS_10/CS") (pintype "bidirectional"))
    )
    (net (code "91") (name "unconnected-(U1-Pad11{slash}MOSI)") (class "Default")
      (node (ref "U1") (pin "11/MOSI") (pinfunction "11/MOSI_11/MOSI") (pintype "bidirectional"))
    )
    (net (code "92") (name "unconnected-(U1-Pad12{slash}MISO)") (class "Default")
      (node (ref "U1") (pin "12/MISO") (pinfunction "12/MISO_12/MISO") (pintype "bidirectional"))
    )
    (net (code "93") (name "unconnected-(U1-Pad13{slash}SCK)") (class "Default")
      (node (ref "U1") (pin "13/SCK") (pinfunction "13/SCK_13/SCK") (pintype "bidirectional"))
    )
    (net (code "94") (name "unconnected-(U1-Pad14{slash}A0)") (class "Default")
      (node (ref "U1") (pin "14/A0") (pinfunction "14/A0_14/A0") (pintype "bidirectional"))
    )
    (net (code "95") (name "unconnected-(U1-Pad15{slash}A1)") (class "Default")
      (node (ref "U1") (pin "15/A1") (pinfunction "15/A1_15/A1") (pintype "bidirectional"))
    )
    (net (code "96") (name "unconnected-(U1-Pad16{slash}A2)") (class "Default")
      (node (ref "U1") (pin "16/A2") (pinfunction "16/A2_16/A2") (pintype "bidirectional"))
    )
    (net (code "97") (name "unconnected-(U1-Pad17{slash}A3)") (class "Default")
      (node (ref "U1") (pin "17/A3") (pinfunction "17/A3_17/A3") (pintype "bidirectional"))
    )
    (net (code "98") (name "unconnected-(U1-Pad18{slash}A4{slash}SDA)") (class "Default")
      (node (ref "U1") (pin "18/A4/SDA") (pinfunction "18/A4/SDA_18/A4/SDA") (pintype "bidirectional"))
    )
    (net (code "99") (name "unconnected-(U1-Pad19{slash}A5{slash}SCL)") (class "Default")
      (node (ref "U1") (pin "19/A5/SCL") (pinfunction "19/A5/SCL_19/A5/SCL") (pintype "bidirectional"))
    )
    (net (code "100") (name "unconnected-(U1-Pad20{slash}A6)") (class "Default")
      (node (ref "U1") (pin "20/A6") (pinfunction "20/A6_20/A6") (pintype "bidirectional"))
    )
    (net (code "101") (name "unconnected-(U1-Pad24)") (class "Default")
      (node (ref "U1") (pin "24") (pinfunction "24_24") (pintype "bidirectional"))
    )
    (net (code "102") (name "unconnected-(U1-Pad25)") (class "Default")
      (node (ref "U1") (pin "25") (pinfunction "25_25") (pintype "bidirectional"))
    )
    (net (code "103") (name "unconnected-(U1-Pad26)") (class "Default")
      (node (ref "U1") (pin "26") (pinfunction "26_26") (pintype "bidirectional"))
    )
    (net (code "104") (name "unconnected-(U1-Pad27)") (class "Default")
      (node (ref "U1") (pin "27") (pinfunction "27_27") (pintype "bidirectional"))
    )
    (net (code "105") (name "unconnected-(U1-Pad28)") (class "Default")
      (node (ref "U1") (pin "28") (pinfunction "28_28") (pintype "bidirectional"))
    )
    (net (code "106") (name "unconnected-(U1-Pad29)") (class "Default")
      (node (ref "U1") (pin "29") (pinfunction "29_29") (pintype "bidirectional"))
    )
    (net (code "107") (name "unconnected-(U1-Pad30)") (class "Default")
      (node (ref "U1") (pin "30") (pinfunction "30_30") (pintype "bidirectional"))
    )
    (net (code "108") (name "unconnected-(U1-Pad31{slash}A12)") (class "Default")
      (node (ref "U1") (pin "31/A12") (pinfunction "31/A12_31/A12") (pintype "bidirectional"))
    )
    (net (code "109") (name "unconnected-(U1-Pad32{slash}A13)") (class "Default")
      (node (ref "U1") (pin "32/A13") (pinfunction "32/A13_32/A13") (pintype "bidirectional"))
    )
    (net (code "110") (name "unconnected-(U1-Pad33{slash}A14)") (class "Default")
      (node (ref "U1") (pin "33/A14") (pinfunction "33/A14_33/A14") (pintype "bidirectional"))
    )
    (net (code "111") (name "unconnected-(U1-Pad34{slash}A15)") (class "Default")
      (node (ref "U1") (pin "34/A15") (pinfunction "34/A15_34/A15") (pintype "bidirectional"))
    )
    (net (code "112") (name "unconnected-(U1-Pad35{slash}A16)") (class "Default")
      (node (ref "U1") (pin "35/A16") (pinfunction "35/A16_35/A16") (pintype "bidirectional"))
    )
    (net (code "113") (name "unconnected-(U1-Pad36{slash}A17)") (class "Default")
      (node (ref "U1") (pin "36/A17") (pinfunction "36/A17_36/A17") (pintype "bidirectional"))
    )
    (net (code "114") (name "unconnected-(U1-Pad37{slash}A18)") (class "Default")
      (node (ref "U1") (pin "37/A18") (pinfunction "37/A18_37/A18") (pintype "bidirectional"))
    )
    (net (code "115") (name "unconnected-(U1-Pad38{slash}A19)") (class "Default")
      (node (ref "U1") (pin "38/A19") (pinfunction "38/A19_38/A19") (pintype "bidirectional"))
    )
    (net (code "116") (name "unconnected-(U1-Pad39{slash}A20)") (class "Default")
      (node (ref "U1") (pin "39/A20") (pinfunction "39/A20_39/A20") (pintype "bidirectional"))
    )
    (net (code "117") (name "unconnected-(U1-PadA10)") (class "Default")
      (node (ref "U1") (pin "A10") (pinfunction "A10_A10") (pintype "bidirectional"))
    )
    (net (code "118") (name "unconnected-(U1-PadA11)") (class "Default")
      (node (ref "U1") (pin "A11") (pinfunction "A11_A11") (pintype "bidirectional"))
    )
    (net (code "119") (name "unconnected-(U1-PadAREF)") (class "Default")
      (node (ref "U1") (pin "AREF") (pinfunction "AREF_AREF") (pintype "bidirectional"))
    )
    (net (code "120") (name "unconnected-(U1-PadGND2)") (class "Default")
      (node (ref "U1") (pin "GND2") (pinfunction "GND2_GND2") (pintype "bidirectional"))
    )
    (net (code "121") (name "unconnected-(U1-PadVUSB)") (class "Default")
      (node (ref "U1") (pin "VUSB") (pinfunction "VUSB_VUSB") (pintype "bidirectional"))
    )
    (net (code "122") (name "unconnected-(U2-D+-Pad4)") (class "Default")
      (node (ref "U2") (pin "4") (pinfunction "D+_4") (pintype "bidirectional"))
    )
    (net (code "123") (name "unconnected-(U2-D--Pad3)") (class "Default")
      (node (ref "U2") (pin "3") (pinfunction "D-_3") (pintype "bidirectional"))
    )
    (net (code "124") (name "unconnected-(U2-PB0(SS)-Pad8)") (class "Default")
      (node (ref "U2") (pin "8") (pinfunction "PB0(SS)_8") (pintype "bidirectional"))
    )
    (net (code "125") (name "unconnected-(U2-PB4(ADC11)-Pad28)") (class "Default")
      (node (ref "U2") (pin "28") (pinfunction "PB4(ADC11)_28") (pintype "bidirectional"))
    )
    (net (code "126") (name "unconnected-(U2-PB5(OC1A{slash}ADC12{slash}~{OC4B})-Pad29)") (class "Default")
      (node (ref "U2") (pin "29") (pinfunction "PB5(OC1A/ADC12/~{OC4B})_29") (pintype "bidirectional"))
    )
    (net (code "127") (name "unconnected-(U2-PB6(OC1B{slash}OC4B{slash}ADC13)-Pad30)") (class "Default")
      (node (ref "U2") (pin "30") (pinfunction "PB6(OC1B/OC4B/ADC13)_30") (pintype "bidirectional"))
    )
    (net (code "128") (name "unconnected-(U2-PB7(OC0A{slash}OC1C{slash}RTS)-Pad12)") (class "Default")
      (node (ref "U2") (pin "12") (pinfunction "PB7(OC0A/OC1C/RTS)_12") (pintype "bidirectional"))
    )
    (net (code "129") (name "unconnected-(U2-PC6(OC3A{slash}~{OC4A})-Pad31)") (class "Default")
      (node (ref "U2") (pin "31") (pinfunction "PC6(OC3A/~{OC4A})_31") (pintype "bidirectional"))
    )
    (net (code "130") (name "unconnected-(U2-PD5(XCK{slash}CTS)-Pad22)") (class "Default")
      (node (ref "U2") (pin "22") (pinfunction "PD5(XCK/CTS)_22") (pintype "bidirectional"))
    )
    (net (code "131") (name "unconnected-(U2-PD6(T1{slash}ADC9{slash}~{OC4D})-Pad26)") (class "Default")
      (node (ref "U2") (pin "26") (pinfunction "PD6(T1/ADC9/~{OC4D})_26") (pintype "bidirectional"))
    )
    (net (code "132") (name "unconnected-(U2-PD7(OC4D{slash}ADC10{slash}T0)-Pad27)") (class "Default")
      (node (ref "U2") (pin "27") (pinfunction "PD7(OC4D/ADC10/T0)_27") (pintype "bidirectional"))
    )
    (net (code "133") (name "unconnected-(U2-PE6(INT.6{slash}AIN0)-Pad1)") (class "Default")
      (node (ref "U2") (pin "1") (pinfunction "PE6(INT.6/AIN0)_1") (pintype "bidirectional"))
    )
    (net (code "134") (name "unconnected-(U2-PF5(ADC5{slash}TMS)-Pad38)") (class "Default")
      (node (ref "U2") (pin "38") (pinfunction "PF5(ADC5/TMS)_38") (pintype "bidirectional"))
    )
    (net (code "135") (name "unconnected-(U2-UCAP-Pad6)") (class "Default")
      (node (ref "U2") (pin "6") (pinfunction "UCAP_6") (pintype "bidirectional"))
    )
    (net (code "136") (name "unconnected-(U2-UGND-Pad5)") (class "Default")
      (node (ref "U2") (pin "5") (pinfunction "UGND_5") (pintype "bidirectional"))
    )
  )
)
